# SparkFun_Dev_ESP32_C3.net
KiCad netlist of a schematic drawn in EAGLE
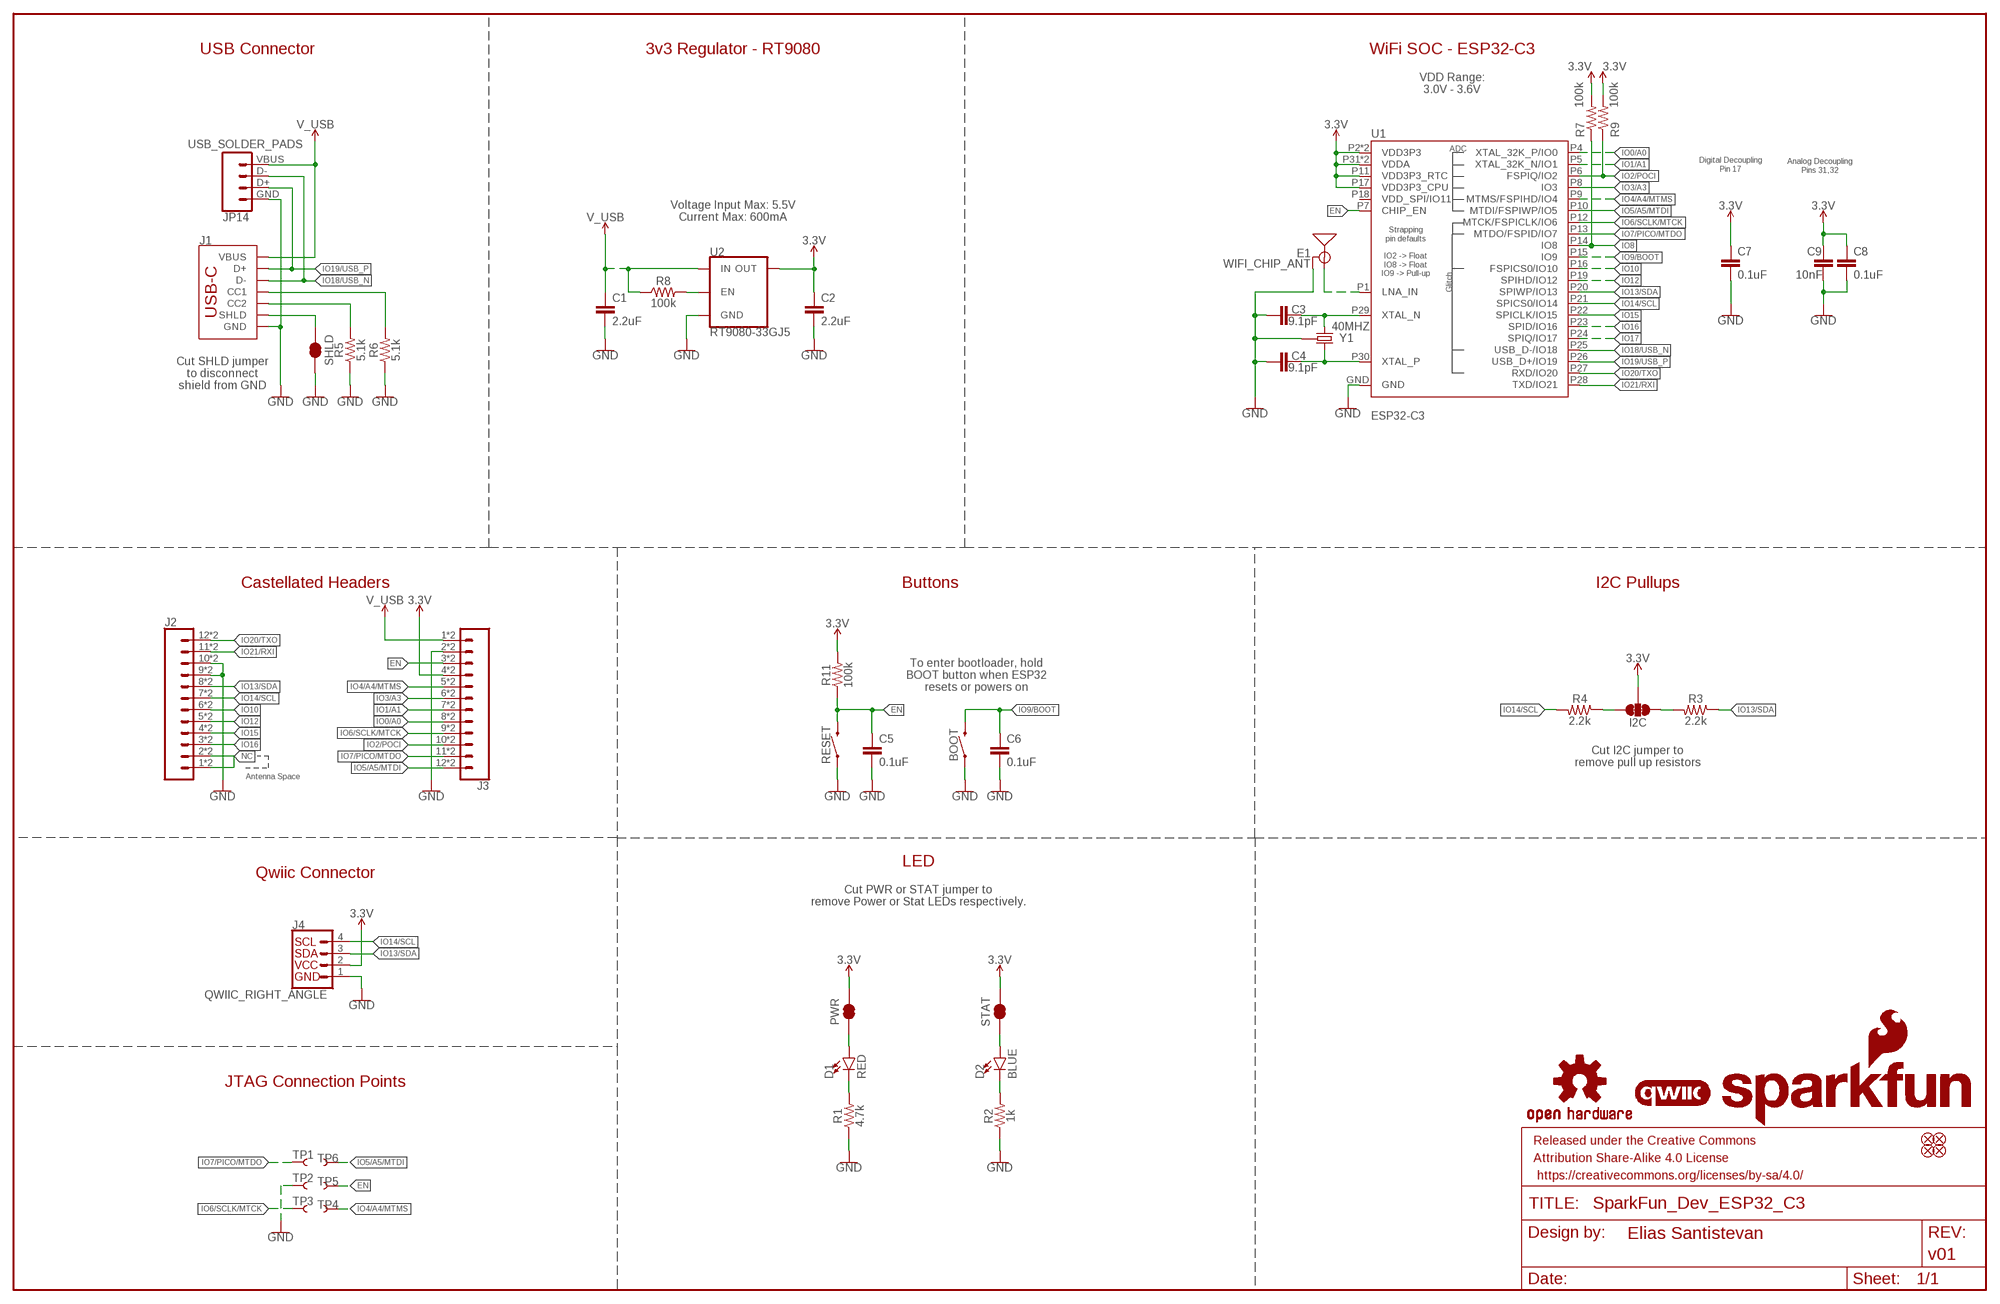
[diagram p0: schematic, sheet 1]

(export (version "E")
  (design (tool "Eeschema 10.0.6"))
  (components
    (comp (ref "BOOT")
      (value "MOMENTARY-SWITCH-SPST-SMD-4.6X2.8MM")
      (footprint "eagle-import:TACTILE_SWITCH_SMD_4.6X2.8MM")
      (libsource (lib "eagle-import") (part "MOMENTARY-SWITCH-SPST-SMD-4.6X2.8MM"))
    )
    (comp (ref "C1")
      (value "2.2uF")
      (footprint "eagle-import:0402-TIGHT")
      (libsource (lib "eagle-import") (part "2.2UF-0402_TIGHT-10V-10%-X5R"))
    )
    (comp (ref "C2")
      (value "2.2uF")
      (footprint "eagle-import:0402-TIGHT")
      (libsource (lib "eagle-import") (part "2.2UF-0402_TIGHT-10V-10%-X5R"))
    )
    (comp (ref "C3")
      (value "9.1pF")
      (footprint "eagle-import:0402-TIGHT")
      (fields (field (name "MOUSER_PART") "609-500R07S9R1CV4T"))
      (libsource (lib "eagle-import") (part "9.1PF-0402-TIGHT"))
    )
    (comp (ref "C4")
      (value "9.1pF")
      (footprint "eagle-import:0402-TIGHT")
      (fields (field (name "MOUSER_PART") "609-500R07S9R1CV4T"))
      (libsource (lib "eagle-import") (part "9.1PF-0402-TIGHT"))
    )
    (comp (ref "C5")
      (value "0.1uF")
      (footprint "eagle-import:0402-TIGHT")
      (libsource (lib "eagle-import") (part "0.1UF-0402T-6.3V-10%-X7R"))
    )
    (comp (ref "C6")
      (value "0.1uF")
      (footprint "eagle-import:0402-TIGHT")
      (libsource (lib "eagle-import") (part "0.1UF-0402T-6.3V-10%-X7R"))
    )
    (comp (ref "C7")
      (value "0.1uF")
      (footprint "eagle-import:0402-TIGHT")
      (libsource (lib "eagle-import") (part "0.1UF-0402T-16V-10%"))
    )
    (comp (ref "C8")
      (value "0.1uF")
      (footprint "eagle-import:0402-TIGHT")
      (libsource (lib "eagle-import") (part "0.1UF-0402T-16V-10%"))
    )
    (comp (ref "C9")
      (value "10nF")
      (footprint "eagle-import:0402-TIGHT")
      (libsource (lib "eagle-import") (part "10NF-0402T-25V-10%"))
    )
    (comp (ref "D1")
      (value "RED")
      (footprint "eagle-import:LED-0603")
      (libsource (lib "eagle-import") (part "LED-RED_0603-KB"))
    )
    (comp (ref "D2")
      (value "BLUE")
      (footprint "eagle-import:LED-0603")
      (libsource (lib "eagle-import") (part "LED-BLUE0603"))
    )
    (comp (ref "E1")
      (value "WIFI_CHIP_ANT")
      (footprint "eagle-import:CHIP_ANT_NO_COURTYARD")
      (libsource (lib "eagle-import") (part "WIFI_CHIP_ANT"))
    )
    (comp (ref "FD1")
      (value "FIDUCIALUFIDUCIAL")
      (footprint "eagle-import:FIDUCIAL-MICRO")
      (libsource (lib "eagle-import") (part "FIDUCIALUFIDUCIAL"))
    )
    (comp (ref "FD2")
      (value "FIDUCIALUFIDUCIAL")
      (footprint "eagle-import:FIDUCIAL-MICRO")
      (libsource (lib "eagle-import") (part "FIDUCIALUFIDUCIAL"))
    )
    (comp (ref "FD3")
      (value "FIDUCIALUFIDUCIAL")
      (footprint "eagle-import:FIDUCIAL-MICRO")
      (libsource (lib "eagle-import") (part "FIDUCIALUFIDUCIAL"))
    )
    (comp (ref "FD4")
      (value "FIDUCIALUFIDUCIAL")
      (footprint "eagle-import:FIDUCIAL-MICRO")
      (libsource (lib "eagle-import") (part "FIDUCIALUFIDUCIAL"))
    )
    (comp (ref "FRAME2")
      (value "FRAME-LEDGER")
      (footprint "eagle-import:CREATIVE_COMMONS")
      (fields (field (name "DESIGNER") "Elias Santistevan") (field (name "REV") "v01"))
      (libsource (lib "eagle-import") (part "FRAME-LEDGER"))
    )
    (comp (ref "I2C")
      (value "JUMPER-SMT_3_2-NC_TRACE_SILK")
      (footprint "eagle-import:SMT-JUMPER_3_2-NC_TRACE_SILK")
      (libsource (lib "eagle-import") (part "JUMPER-SMT_3_2-NC_TRACE_SILK"))
    )
    (comp (ref "J1")
      (value "USB Female Type C Connector")
      (footprint "eagle-import:USB-C-16P_4LAYER-PADS")
      (libsource (lib "eagle-import") (part "USB_C_4-LAYER_PADS"))
    )
    (comp (ref "J2")
      (value "CONN_12CASTELLATED")
      (footprint "eagle-import:1X12_CASTELLATED")
      (libsource (lib "eagle-import") (part "CONN_12CASTELLATED"))
    )
    (comp (ref "J3")
      (value "CONN_12CASTELLATED")
      (footprint "eagle-import:1X12_CASTELLATED")
      (libsource (lib "eagle-import") (part "CONN_12CASTELLATED"))
    )
    (comp (ref "J4")
      (value "QWIIC_RIGHT_ANGLE")
      (footprint "eagle-import:JST04_1MM_RA")
      (libsource (lib "eagle-import") (part "QWIIC_CONNECTORJS-1MM"))
    )
    (comp (ref "JP14")
      (value "USB_SOLDER_PADS")
      (footprint "eagle-import:USB-SOLDER-PADS")
      (libsource (lib "eagle-import") (part "USB_SOLDER_PADS"))
    )
    (comp (ref "LOGO1")
      (value "SFE_LOGO_NAME_FLAMEBLANK")
      (footprint "eagle-import:BLANK")
      (libsource (lib "eagle-import") (part "SFE_LOGO_NAME_FLAMEBLANK"))
    )
    (comp (ref "LOGO2")
      (value "QWIIC_LOGO_3MM")
      (footprint "eagle-import:QWIIC_3MM")
      (libsource (lib "eagle-import") (part "QWIIC_LOGO_3MM"))
    )
    (comp (ref "LOGO3")
      (value "OSHW-LOGOS")
      (footprint "eagle-import:OSHW-LOGO-S")
      (libsource (lib "eagle-import") (part "OSHW-LOGOS"))
    )
    (comp (ref "PWR")
      (value "JUMPER-SMT_2_NC_TRACE_SILK")
      (footprint "eagle-import:SMT-JUMPER_2_NC_TRACE_SILK")
      (libsource (lib "eagle-import") (part "JUMPER-SMT_2_NC_TRACE_SILK"))
    )
    (comp (ref "R1")
      (value "4.7k")
      (footprint "eagle-import:0402-TIGHT")
      (libsource (lib "eagle-import") (part "4.7KOHM-0402T-1/16W-1%"))
    )
    (comp (ref "R2")
      (value "1k")
      (footprint "eagle-import:0402-TIGHT")
      (libsource (lib "eagle-import") (part "1KOHM-0402T-1/16W-1%"))
    )
    (comp (ref "R3")
      (value "2.2k")
      (footprint "eagle-import:0402-TIGHT")
      (libsource (lib "eagle-import") (part "2.2KOHM-0402T-1/16W-1%"))
    )
    (comp (ref "R4")
      (value "2.2k")
      (footprint "eagle-import:0402-TIGHT")
      (libsource (lib "eagle-import") (part "2.2KOHM-0402T-1/16W-1%"))
    )
    (comp (ref "R5")
      (value "5.1k")
      (footprint "eagle-import:0402-TIGHT")
      (libsource (lib "eagle-import") (part "5.1KOHM-0402T-1/16W-1%"))
    )
    (comp (ref "R6")
      (value "5.1k")
      (footprint "eagle-import:0402-TIGHT")
      (libsource (lib "eagle-import") (part "5.1KOHM-0402T-1/16W-1%"))
    )
    (comp (ref "R7")
      (value "100k")
      (footprint "eagle-import:0402-TIGHT")
      (libsource (lib "eagle-import") (part "100KOHM-0402T-1/16W-1%"))
    )
    (comp (ref "R8")
      (value "100k")
      (footprint "eagle-import:0402-TIGHT")
      (libsource (lib "eagle-import") (part "100KOHM-0402T-1/16W-1%"))
    )
    (comp (ref "R9")
      (value "100k")
      (footprint "eagle-import:0402-TIGHT")
      (libsource (lib "eagle-import") (part "100KOHM-0402T-1/16W-1%"))
    )
    (comp (ref "R11")
      (value "100k")
      (footprint "eagle-import:0402-TIGHT")
      (libsource (lib "eagle-import") (part "100KOHM-0402T-1/16W-1%"))
    )
    (comp (ref "RESET")
      (value "MOMENTARY-SWITCH-SPST-SMD-4.6X2.8MM")
      (footprint "eagle-import:TACTILE_SWITCH_SMD_4.6X2.8MM")
      (libsource (lib "eagle-import") (part "MOMENTARY-SWITCH-SPST-SMD-4.6X2.8MM"))
    )
    (comp (ref "SHLD")
      (value "JUMPER-SMT_2_NC_TRACE_SILK")
      (footprint "eagle-import:SMT-JUMPER_2_NC_TRACE_SILK")
      (libsource (lib "eagle-import") (part "JUMPER-SMT_2_NC_TRACE_SILK"))
    )
    (comp (ref "STAT")
      (value "JUMPER-SMT_2_NC_TRACE_SILK")
      (footprint "eagle-import:SMT-JUMPER_2_NC_TRACE_SILK")
      (libsource (lib "eagle-import") (part "JUMPER-SMT_2_NC_TRACE_SILK"))
    )
    (comp (ref "TP1")
      (value "TEST-POINT3X5")
      (footprint "eagle-import:PAD.03X.05")
      (libsource (lib "eagle-import") (part "TEST-POINT3X5"))
    )
    (comp (ref "TP2")
      (value "TEST-POINT3X5")
      (footprint "eagle-import:PAD.03X.05")
      (libsource (lib "eagle-import") (part "TEST-POINT3X5"))
    )
    (comp (ref "TP3")
      (value "TEST-POINT3X5")
      (footprint "eagle-import:PAD.03X.05")
      (libsource (lib "eagle-import") (part "TEST-POINT3X5"))
    )
    (comp (ref "TP4")
      (value "TEST-POINT3X5")
      (footprint "eagle-import:PAD.03X.05")
      (libsource (lib "eagle-import") (part "TEST-POINT3X5"))
    )
    (comp (ref "TP5")
      (value "TEST-POINT3X5")
      (footprint "eagle-import:PAD.03X.05")
      (libsource (lib "eagle-import") (part "TEST-POINT3X5"))
    )
    (comp (ref "TP6")
      (value "TEST-POINT3X5")
      (footprint "eagle-import:PAD.03X.05")
      (libsource (lib "eagle-import") (part "TEST-POINT3X5"))
    )
    (comp (ref "U1")
      (value "ESP32-C3")
      (footprint "eagle-import:QFN32")
      (libsource (lib "eagle-import") (part "ESP32-C3"))
    )
    (comp (ref "U2")
      (value "RT9080-33GJ5")
      (footprint "eagle-import:SOT23-5")
      (libsource (lib "eagle-import") (part "V_REG_RT9080"))
    )
    (comp (ref "Y1")
      (value "40MHZ")
      (footprint "eagle-import:CRYSTAL-SMD-2X2.5MM")
      (libsource (lib "eagle-import") (part "CRYSTAL-40MHZ-SMD-2X2.5MM"))
    )
  )
  (nets
    (net (code "1") (name "3.3V") (class "Default")
      (node (ref "C2") (pin "1") (pinfunction "1_1") (pintype "passive"))
      (node (ref "C7") (pin "1") (pinfunction "1_1") (pintype "passive"))
      (node (ref "C8") (pin "1") (pinfunction "1_1") (pintype "passive"))
      (node (ref "C9") (pin "1") (pinfunction "1_1") (pintype "passive"))
      (node (ref "I2C") (pin "2") (pinfunction "2_2") (pintype "passive"))
      (node (ref "J3") (pin "4") (pinfunction "4_4") (pintype "passive"))
      (node (ref "J3") (pin "4B") (pinfunction "4_4B") (pintype "passive"))
      (node (ref "J4") (pin "2") (pinfunction "2_2") (pintype "power_in"))
      (node (ref "PWR") (pin "2") (pinfunction "2_2") (pintype "passive"))
      (node (ref "R11") (pin "2") (pinfunction "2_2") (pintype "passive"))
      (node (ref "R7") (pin "2") (pinfunction "2_2") (pintype "passive"))
      (node (ref "R9") (pin "2") (pinfunction "2_2") (pintype "passive"))
      (node (ref "STAT") (pin "2") (pinfunction "2_2") (pintype "passive"))
      (node (ref "U1") (pin "P11") (pinfunction "VDD3P3_RTC_P11") (pintype "bidirectional"))
      (node (ref "U1") (pin "P17") (pinfunction "VDD3P3_CPU_P17") (pintype "bidirectional"))
      (node (ref "U1") (pin "P2") (pinfunction "VDD3P3_P2") (pintype "bidirectional"))
      (node (ref "U1") (pin "P3") (pinfunction "VDD3P3_P3") (pintype "bidirectional"))
      (node (ref "U1") (pin "P31") (pinfunction "VDDA_P31") (pintype "bidirectional"))
      (node (ref "U1") (pin "P32") (pinfunction "VDDA_P32") (pintype "bidirectional"))
      (node (ref "U2") (pin "5") (pinfunction "OUT_5") (pintype "passive"))
    )
    (net (code "2") (name "EN") (class "Default")
      (node (ref "C5") (pin "1") (pinfunction "1_1") (pintype "passive"))
      (node (ref "J3") (pin "3") (pinfunction "3_3") (pintype "passive"))
      (node (ref "J3") (pin "3B") (pinfunction "3_3B") (pintype "passive"))
      (node (ref "R11") (pin "1") (pinfunction "1_1") (pintype "passive"))
      (node (ref "RESET") (pin "3") (pinfunction "2_3") (pintype "passive"))
      (node (ref "RESET") (pin "4") (pinfunction "2_4") (pintype "passive"))
      (node (ref "TP5") (pin "1") (pinfunction "1_1") (pintype "bidirectional"))
      (node (ref "U1") (pin "P7") (pinfunction "CHIP_EN_P7") (pintype "bidirectional"))
    )
    (net (code "3") (name "GND") (class "Default")
      (node (ref "BOOT") (pin "1") (pinfunction "1_1") (pintype "passive"))
      (node (ref "BOOT") (pin "2") (pinfunction "1_2") (pintype "passive"))
      (node (ref "C1") (pin "2") (pinfunction "2_2") (pintype "passive"))
      (node (ref "C2") (pin "2") (pinfunction "2_2") (pintype "passive"))
      (node (ref "C3") (pin "1") (pinfunction "1_1") (pintype "passive"))
      (node (ref "C4") (pin "1") (pinfunction "1_1") (pintype "passive"))
      (node (ref "C5") (pin "2") (pinfunction "2_2") (pintype "passive"))
      (node (ref "C6") (pin "2") (pinfunction "2_2") (pintype "passive"))
      (node (ref "C7") (pin "2") (pinfunction "2_2") (pintype "passive"))
      (node (ref "C8") (pin "2") (pinfunction "2_2") (pintype "passive"))
      (node (ref "C9") (pin "2") (pinfunction "2_2") (pintype "passive"))
      (node (ref "E1") (pin "P3") (pinfunction "GND_P3") (pintype "bidirectional"))
      (node (ref "E1") (pin "P4") (pinfunction "GND_P4") (pintype "bidirectional"))
      (node (ref "J1") (pin "GND") (pinfunction "GND_GND") (pintype "bidirectional"))
      (node (ref "J1") (pin "GND2") (pinfunction "GND_GND2") (pintype "bidirectional"))
      (node (ref "J2") (pin "10") (pinfunction "10_10") (pintype "passive"))
      (node (ref "J2") (pin "10B") (pinfunction "10_10B") (pintype "passive"))
      (node (ref "J2") (pin "9") (pinfunction "9_9") (pintype "passive"))
      (node (ref "J2") (pin "9B") (pinfunction "9_9B") (pintype "passive"))
      (node (ref "J3") (pin "2") (pinfunction "2_2") (pintype "passive"))
      (node (ref "J3") (pin "2B") (pinfunction "2_2B") (pintype "passive"))
      (node (ref "J4") (pin "1") (pinfunction "1_1") (pintype "power_in"))
      (node (ref "JP14") (pin "GND") (pinfunction "4_GND") (pintype "passive"))
      (node (ref "R1") (pin "1") (pinfunction "1_1") (pintype "passive"))
      (node (ref "R2") (pin "1") (pinfunction "1_1") (pintype "passive"))
      (node (ref "R5") (pin "1") (pinfunction "1_1") (pintype "passive"))
      (node (ref "R6") (pin "1") (pinfunction "1_1") (pintype "passive"))
      (node (ref "RESET") (pin "1") (pinfunction "1_1") (pintype "passive"))
      (node (ref "RESET") (pin "2") (pinfunction "1_2") (pintype "passive"))
      (node (ref "SHLD") (pin "2") (pinfunction "2_2") (pintype "passive"))
      (node (ref "TP2") (pin "1") (pinfunction "1_1") (pintype "bidirectional"))
      (node (ref "U1") (pin "GND") (pinfunction "GND_GND") (pintype "bidirectional"))
      (node (ref "U2") (pin "2") (pinfunction "GND_2") (pintype "input"))
      (node (ref "Y1") (pin "P2") (pinfunction "GND_P2") (pintype "power_in"))
      (node (ref "Y1") (pin "P4") (pinfunction "GND_P4") (pintype "power_in"))
    )
    (net (code "4") (name "IO0{slash}A0") (class "Default")
      (node (ref "J3") (pin "8") (pinfunction "8_8") (pintype "passive"))
      (node (ref "J3") (pin "8B") (pinfunction "8_8B") (pintype "passive"))
      (node (ref "U1") (pin "P4") (pinfunction "XTAL_32K_P/IO0_P4") (pintype "bidirectional"))
    )
    (net (code "5") (name "IO1{slash}A1") (class "Default")
      (node (ref "J3") (pin "7") (pinfunction "7_7") (pintype "passive"))
      (node (ref "J3") (pin "7B") (pinfunction "7_7B") (pintype "passive"))
      (node (ref "U1") (pin "P5") (pinfunction "XTAL_32K_N/IO1_P5") (pintype "bidirectional"))
    )
    (net (code "6") (name "IO2{slash}POCI") (class "Default")
      (node (ref "J3") (pin "10") (pinfunction "10_10") (pintype "passive"))
      (node (ref "J3") (pin "10B") (pinfunction "10_10B") (pintype "passive"))
      (node (ref "R9") (pin "1") (pinfunction "1_1") (pintype "passive"))
      (node (ref "U1") (pin "P6") (pinfunction "FSPIQ/IO2_P6") (pintype "bidirectional"))
    )
    (net (code "7") (name "IO3{slash}A3") (class "Default")
      (node (ref "J3") (pin "6") (pinfunction "6_6") (pintype "passive"))
      (node (ref "J3") (pin "6B") (pinfunction "6_6B") (pintype "passive"))
      (node (ref "U1") (pin "P8") (pinfunction "IO3_P8") (pintype "bidirectional"))
    )
    (net (code "8") (name "IO4{slash}A4{slash}MTMS") (class "Default")
      (node (ref "J3") (pin "5") (pinfunction "5_5") (pintype "passive"))
      (node (ref "J3") (pin "5B") (pinfunction "5_5B") (pintype "passive"))
      (node (ref "TP4") (pin "1") (pinfunction "1_1") (pintype "bidirectional"))
      (node (ref "U1") (pin "P9") (pinfunction "MTMS/FSPIHD/IO4_P9") (pintype "bidirectional"))
    )
    (net (code "9") (name "IO5{slash}A5{slash}MTDI") (class "Default")
      (node (ref "J3") (pin "12") (pinfunction "12_12") (pintype "passive"))
      (node (ref "J3") (pin "12B") (pinfunction "12_12B") (pintype "passive"))
      (node (ref "TP6") (pin "1") (pinfunction "1_1") (pintype "bidirectional"))
      (node (ref "U1") (pin "P10") (pinfunction "MTDI/FSPIWP/IO5_P10") (pintype "bidirectional"))
    )
    (net (code "10") (name "IO6{slash}SCLK{slash}MTCK") (class "Default")
      (node (ref "J3") (pin "9") (pinfunction "9_9") (pintype "passive"))
      (node (ref "J3") (pin "9B") (pinfunction "9_9B") (pintype "passive"))
      (node (ref "TP3") (pin "1") (pinfunction "1_1") (pintype "bidirectional"))
      (node (ref "U1") (pin "P12") (pinfunction "MTCK/FSPICLK/IO6_P12") (pintype "bidirectional"))
    )
    (net (code "11") (name "IO7{slash}PICO{slash}MTDO") (class "Default")
      (node (ref "J3") (pin "11") (pinfunction "11_11") (pintype "passive"))
      (node (ref "J3") (pin "11B") (pinfunction "11_11B") (pintype "passive"))
      (node (ref "TP1") (pin "1") (pinfunction "1_1") (pintype "bidirectional"))
      (node (ref "U1") (pin "P13") (pinfunction "MTDO/FSPID/IO7_P13") (pintype "bidirectional"))
    )
    (net (code "12") (name "IO8") (class "Default")
      (node (ref "R7") (pin "1") (pinfunction "1_1") (pintype "passive"))
      (node (ref "U1") (pin "P14") (pinfunction "IO8_P14") (pintype "bidirectional"))
    )
    (net (code "13") (name "IO9{slash}BOOT") (class "Default")
      (node (ref "BOOT") (pin "3") (pinfunction "2_3") (pintype "passive"))
      (node (ref "BOOT") (pin "4") (pinfunction "2_4") (pintype "passive"))
      (node (ref "C6") (pin "1") (pinfunction "1_1") (pintype "passive"))
      (node (ref "U1") (pin "P15") (pinfunction "IO9_P15") (pintype "bidirectional"))
    )
    (net (code "14") (name "IO10") (class "Default")
      (node (ref "J2") (pin "6") (pinfunction "6_6") (pintype "passive"))
      (node (ref "J2") (pin "6B") (pinfunction "6_6B") (pintype "passive"))
      (node (ref "U1") (pin "P16") (pinfunction "FSPICS0/IO10_P16") (pintype "bidirectional"))
    )
    (net (code "15") (name "IO12") (class "Default")
      (node (ref "J2") (pin "5") (pinfunction "5_5") (pintype "passive"))
      (node (ref "J2") (pin "5B") (pinfunction "5_5B") (pintype "passive"))
      (node (ref "U1") (pin "P19") (pinfunction "SPIHD/IO12_P19") (pintype "bidirectional"))
    )
    (net (code "16") (name "IO13{slash}SDA") (class "Default")
      (node (ref "J2") (pin "8") (pinfunction "8_8") (pintype "passive"))
      (node (ref "J2") (pin "8B") (pinfunction "8_8B") (pintype "passive"))
      (node (ref "J4") (pin "3") (pinfunction "3_3") (pintype "passive"))
      (node (ref "R3") (pin "1") (pinfunction "1_1") (pintype "passive"))
      (node (ref "U1") (pin "P20") (pinfunction "SPIWP/IO13_P20") (pintype "bidirectional"))
    )
    (net (code "17") (name "IO14{slash}SCL") (class "Default")
      (node (ref "J2") (pin "7") (pinfunction "7_7") (pintype "passive"))
      (node (ref "J2") (pin "7B") (pinfunction "7_7B") (pintype "passive"))
      (node (ref "J4") (pin "4") (pinfunction "4_4") (pintype "passive"))
      (node (ref "R4") (pin "2") (pinfunction "2_2") (pintype "passive"))
      (node (ref "U1") (pin "P21") (pinfunction "SPICS0/IO14_P21") (pintype "bidirectional"))
    )
    (net (code "18") (name "IO15") (class "Default")
      (node (ref "J2") (pin "4") (pinfunction "4_4") (pintype "passive"))
      (node (ref "J2") (pin "4B") (pinfunction "4_4B") (pintype "passive"))
      (node (ref "U1") (pin "P22") (pinfunction "SPICLK/IO15_P22") (pintype "bidirectional"))
    )
    (net (code "19") (name "IO16") (class "Default")
      (node (ref "J2") (pin "3") (pinfunction "3_3") (pintype "passive"))
      (node (ref "J2") (pin "3B") (pinfunction "3_3B") (pintype "passive"))
      (node (ref "U1") (pin "P23") (pinfunction "SPID/IO16_P23") (pintype "bidirectional"))
    )
    (net (code "20") (name "IO17") (class "Default")
      (node (ref "U1") (pin "P24") (pinfunction "SPIQ/IO17_P24") (pintype "bidirectional"))
    )
    (net (code "21") (name "IO18{slash}USB_N") (class "Default")
      (node (ref "J1") (pin "A7") (pinfunction "D-_A7") (pintype "bidirectional"))
      (node (ref "J1") (pin "B7") (pinfunction "D-_B7") (pintype "bidirectional"))
      (node (ref "JP14") (pin "D-") (pinfunction "2_D-") (pintype "passive"))
      (node (ref "U1") (pin "P25") (pinfunction "USB_D-/IO18_P25") (pintype "bidirectional"))
    )
    (net (code "22") (name "IO19{slash}USB_P") (class "Default")
      (node (ref "J1") (pin "A6") (pinfunction "D+_A6") (pintype "bidirectional"))
      (node (ref "J1") (pin "B6") (pinfunction "D+_B6") (pintype "bidirectional"))
      (node (ref "JP14") (pin "D+") (pinfunction "3_D+") (pintype "passive"))
      (node (ref "U1") (pin "P26") (pinfunction "USB_D+/IO19_P26") (pintype "bidirectional"))
    )
    (net (code "23") (name "IO20{slash}TXO") (class "Default")
      (node (ref "J2") (pin "12") (pinfunction "12_12") (pintype "passive"))
      (node (ref "J2") (pin "12B") (pinfunction "12_12B") (pintype "passive"))
      (node (ref "U1") (pin "P27") (pinfunction "RXD/IO20_P27") (pintype "bidirectional"))
    )
    (net (code "24") (name "IO21{slash}RXI") (class "Default")
      (node (ref "J2") (pin "11") (pinfunction "11_11") (pintype "passive"))
      (node (ref "J2") (pin "11B") (pinfunction "11_11B") (pintype "passive"))
      (node (ref "U1") (pin "P28") (pinfunction "TXD/IO21_P28") (pintype "bidirectional"))
    )
    (net (code "25") (name "NC") (class "Default")
      (node (ref "J2") (pin "1") (pinfunction "1_1") (pintype "passive"))
      (node (ref "J2") (pin "1B") (pinfunction "1_1B") (pintype "passive"))
      (node (ref "J2") (pin "2") (pinfunction "2_2") (pintype "passive"))
      (node (ref "J2") (pin "2B") (pinfunction "2_2B") (pintype "passive"))
    )
    (net (code "26") (name "Net-(D1-PadA)") (class "Default")
      (node (ref "D1") (pin "A") (pinfunction "A_A") (pintype "passive"))
      (node (ref "PWR") (pin "1") (pinfunction "1_1") (pintype "passive"))
    )
    (net (code "27") (name "Net-(D1-PadC)") (class "Default")
      (node (ref "D1") (pin "C") (pinfunction "C_C") (pintype "passive"))
      (node (ref "R1") (pin "2") (pinfunction "2_2") (pintype "passive"))
    )
    (net (code "28") (name "Net-(D2-PadA)") (class "Default")
      (node (ref "D2") (pin "A") (pinfunction "A_A") (pintype "passive"))
      (node (ref "STAT") (pin "1") (pinfunction "1_1") (pintype "passive"))
    )
    (net (code "29") (name "Net-(D2-PadC)") (class "Default")
      (node (ref "D2") (pin "C") (pinfunction "C_C") (pintype "passive"))
      (node (ref "R2") (pin "2") (pinfunction "2_2") (pintype "passive"))
    )
    (net (code "30") (name "Net-(E1-SIGNAL)") (class "Default")
      (node (ref "E1") (pin "P1") (pinfunction "SIGNAL_P1") (pintype "bidirectional"))
      (node (ref "U1") (pin "P1") (pinfunction "LNA_IN_P1") (pintype "bidirectional"))
    )
    (net (code "31") (name "Net-(I2C-Pad1)") (class "Default")
      (node (ref "I2C") (pin "1") (pinfunction "1_1") (pintype "passive"))
      (node (ref "R4") (pin "1") (pinfunction "1_1") (pintype "passive"))
    )
    (net (code "32") (name "Net-(I2C-Pad3)") (class "Default")
      (node (ref "I2C") (pin "3") (pinfunction "3_3") (pintype "passive"))
      (node (ref "R3") (pin "2") (pinfunction "2_2") (pintype "passive"))
    )
    (net (code "33") (name "Net-(J1-CC1)") (class "Default")
      (node (ref "J1") (pin "A5") (pinfunction "CC1_A5") (pintype "bidirectional"))
      (node (ref "R6") (pin "2") (pinfunction "2_2") (pintype "passive"))
    )
    (net (code "34") (name "Net-(J1-CC2)") (class "Default")
      (node (ref "J1") (pin "B5") (pinfunction "CC2_B5") (pintype "bidirectional"))
      (node (ref "R5") (pin "2") (pinfunction "2_2") (pintype "passive"))
    )
    (net (code "35") (name "Net-(J1-SHLD-PadSHLD1)") (class "Default")
      (node (ref "J1") (pin "SHLD1") (pinfunction "SHLD_SHLD1") (pintype "bidirectional"))
      (node (ref "J1") (pin "SHLD2") (pinfunction "SHLD_SHLD2") (pintype "bidirectional"))
      (node (ref "J1") (pin "SHLD3") (pinfunction "SHLD_SHLD3") (pintype "bidirectional"))
      (node (ref "J1") (pin "SHLD4") (pinfunction "SHLD_SHLD4") (pintype "bidirectional"))
      (node (ref "SHLD") (pin "1") (pinfunction "1_1") (pintype "passive"))
    )
    (net (code "36") (name "Net-(U1-XTAL_N)") (class "Default")
      (node (ref "C3") (pin "2") (pinfunction "2_2") (pintype "passive"))
      (node (ref "U1") (pin "P29") (pinfunction "XTAL_N_P29") (pintype "bidirectional"))
      (node (ref "Y1") (pin "P1") (pinfunction "1_P1") (pintype "passive"))
    )
    (net (code "37") (name "Net-(U1-XTAL_P)") (class "Default")
      (node (ref "C4") (pin "2") (pinfunction "2_2") (pintype "passive"))
      (node (ref "U1") (pin "P30") (pinfunction "XTAL_P_P30") (pintype "bidirectional"))
      (node (ref "Y1") (pin "P3") (pinfunction "2_P3") (pintype "passive"))
    )
    (net (code "38") (name "Net-(U2-EN)") (class "Default")
      (node (ref "R8") (pin "2") (pinfunction "2_2") (pintype "passive"))
      (node (ref "U2") (pin "3") (pinfunction "EN_3") (pintype "input"))
    )
    (net (code "39") (name "V_USB") (class "Default")
      (node (ref "C1") (pin "1") (pinfunction "1_1") (pintype "passive"))
      (node (ref "J1") (pin "VBUS1") (pinfunction "VBUS_VBUS1") (pintype "bidirectional"))
      (node (ref "J1") (pin "VBUS2") (pinfunction "VBUS_VBUS2") (pintype "bidirectional"))
      (node (ref "J3") (pin "1") (pinfunction "1_1") (pintype "passive"))
      (node (ref "J3") (pin "1B") (pinfunction "1_1B") (pintype "passive"))
      (node (ref "JP14") (pin "VBUS") (pinfunction "1_VBUS") (pintype "passive"))
      (node (ref "R8") (pin "1") (pinfunction "1_1") (pintype "passive"))
      (node (ref "U2") (pin "1") (pinfunction "IN_1") (pintype "input"))
    )
    (net (code "40") (name "unconnected-(U1-VDD_SPI{slash}IO11-PadP18)") (class "Default")
      (node (ref "U1") (pin "P18") (pinfunction "VDD_SPI/IO11_P18") (pintype "bidirectional"))
    )
  )
)
